# ministore-interconnect.net
KiCad netlist of a schematic drawn in EAGLE
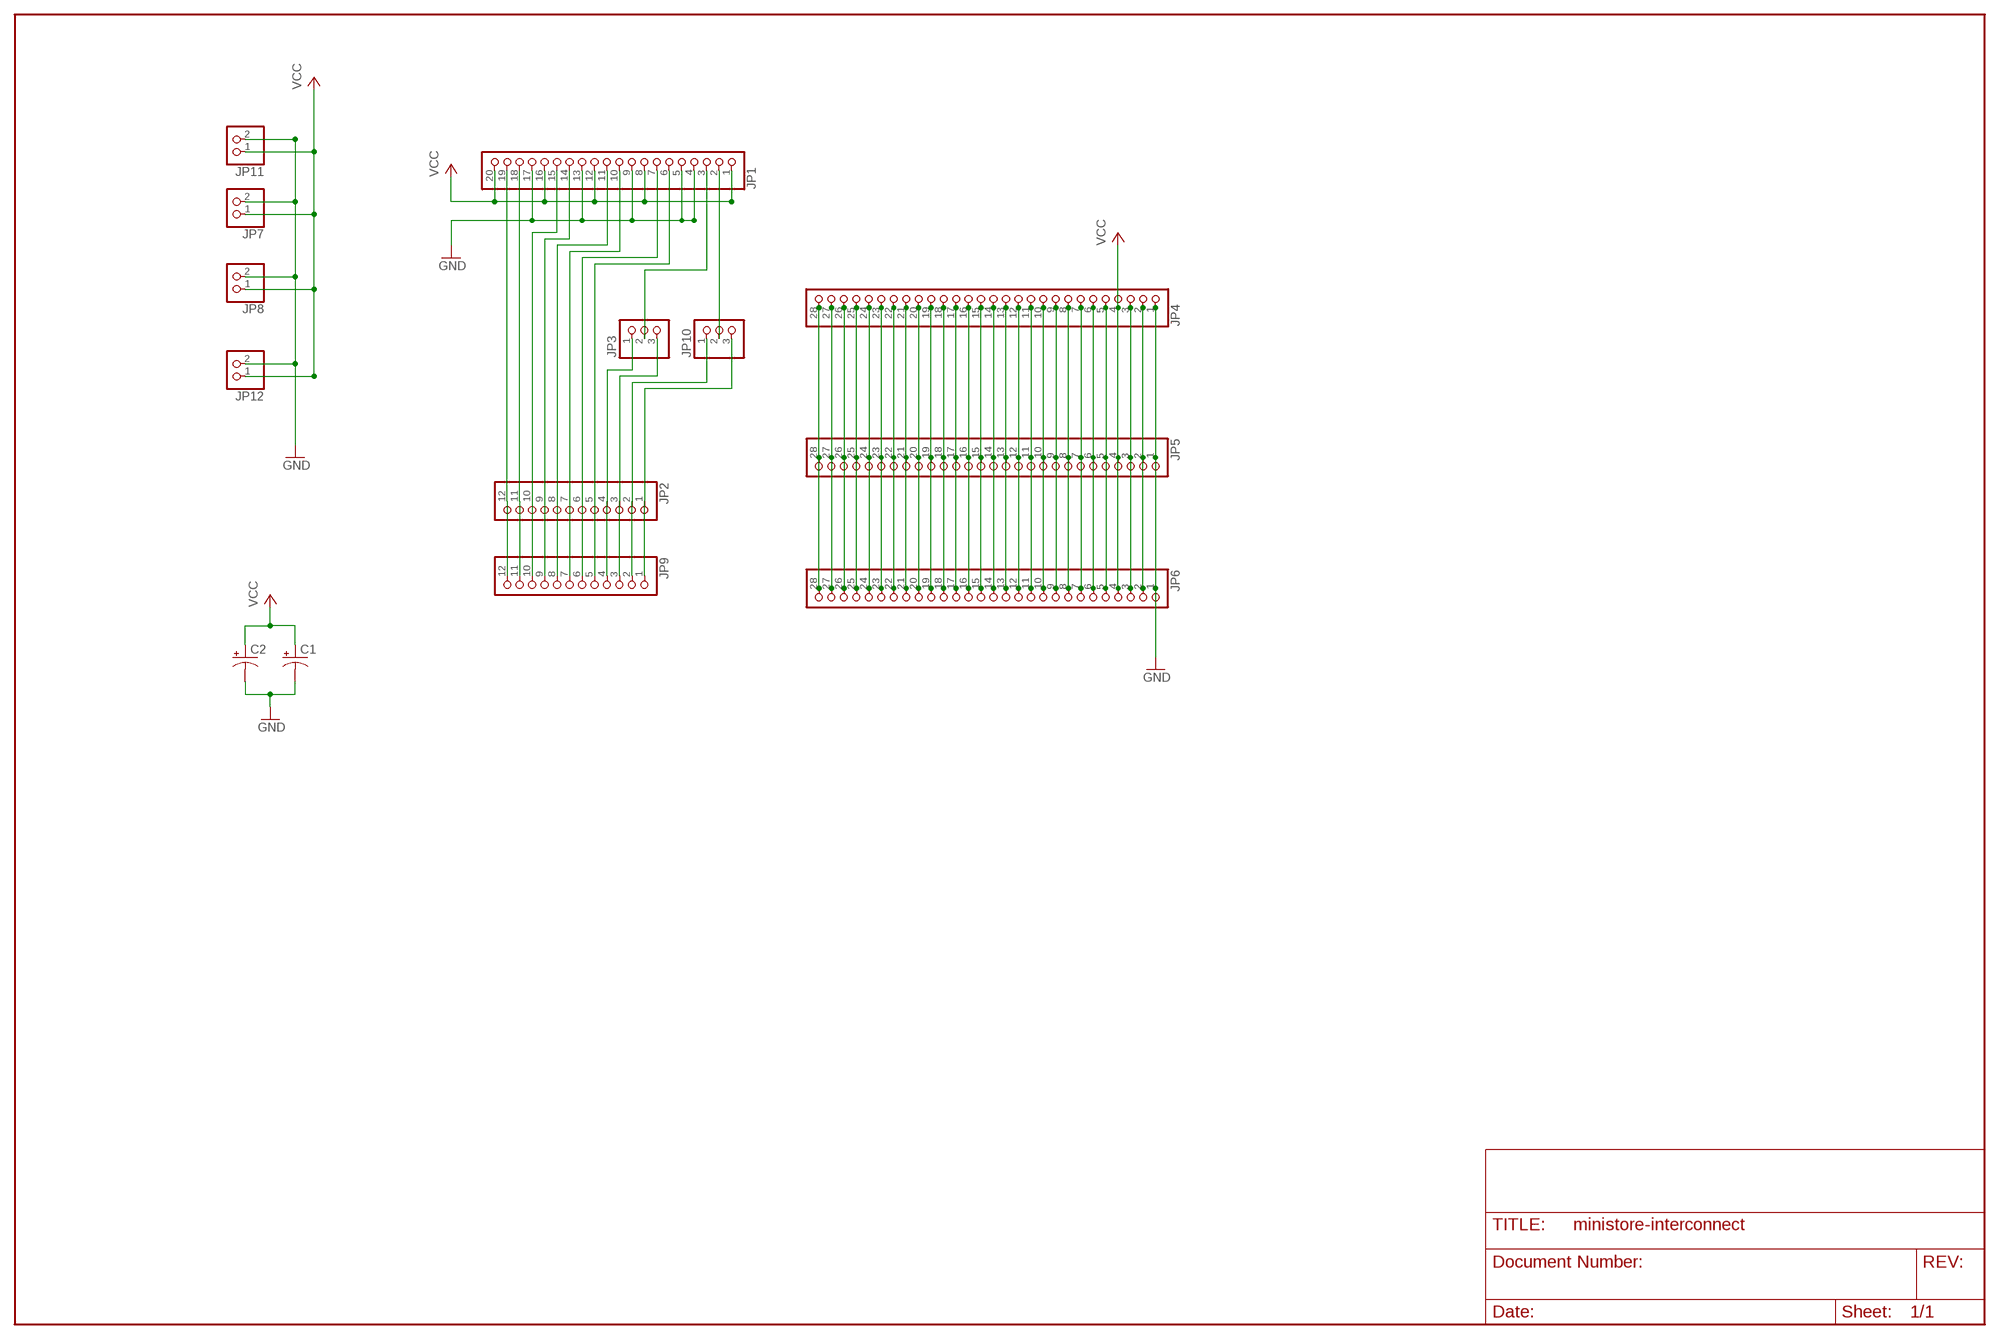
[diagram p0: schematic, sheet 1]

(export (version "E")
  (design (tool "Eeschema 10.0.6"))
  (components
    (comp (ref "C1")
      (value "CPOL-USE15-6AXIAL")
      (footprint "eagle-import:E15-6")
      (libsource (lib "eagle-import") (part "CPOL-USE15-6AXIAL"))
    )
    (comp (ref "C2")
      (value "CPOL-USE15-6AXIAL")
      (footprint "eagle-import:E15-6")
      (libsource (lib "eagle-import") (part "CPOL-USE15-6AXIAL"))
    )
    (comp (ref "JP1")
      (value "PINHD-1X20")
      (footprint "eagle-import:1X20")
      (libsource (lib "eagle-import") (part "PINHD-1X20"))
    )
    (comp (ref "JP2")
      (value "PINHD-1X12")
      (footprint "eagle-import:1X12")
      (libsource (lib "eagle-import") (part "PINHD-1X12"))
    )
    (comp (ref "JP3")
      (value "PINHD-1X3")
      (footprint "eagle-import:1X03")
      (libsource (lib "eagle-import") (part "PINHD-1X3"))
    )
    (comp (ref "JP4")
      (value "PINHD-1X28")
      (footprint "eagle-import:1X28")
      (libsource (lib "eagle-import") (part "PINHD-1X28"))
    )
    (comp (ref "JP5")
      (value "PINHD-1X28")
      (footprint "eagle-import:1X28")
      (libsource (lib "eagle-import") (part "PINHD-1X28"))
    )
    (comp (ref "JP6")
      (value "PINHD-1X28")
      (footprint "eagle-import:1X28")
      (libsource (lib "eagle-import") (part "PINHD-1X28"))
    )
    (comp (ref "JP7")
      (value "PINHD-1X2")
      (footprint "eagle-import:1X02")
      (libsource (lib "eagle-import") (part "PINHD-1X2"))
    )
    (comp (ref "JP8")
      (value "PINHD-1X2")
      (footprint "eagle-import:1X02")
      (libsource (lib "eagle-import") (part "PINHD-1X2"))
    )
    (comp (ref "JP9")
      (value "PINHD-1X12")
      (footprint "eagle-import:1X12")
      (libsource (lib "eagle-import") (part "PINHD-1X12"))
    )
    (comp (ref "JP10")
      (value "PINHD-1X3")
      (footprint "eagle-import:1X03")
      (libsource (lib "eagle-import") (part "PINHD-1X3"))
    )
    (comp (ref "JP11")
      (value "PINHD-1X2")
      (footprint "eagle-import:1X02")
      (libsource (lib "eagle-import") (part "PINHD-1X2"))
    )
    (comp (ref "JP12")
      (value "PINHD-1X2")
      (footprint "eagle-import:1X02")
      (libsource (lib "eagle-import") (part "PINHD-1X2"))
    )
  )
  (nets
    (net (code "1") (name "GND") (class "Default")
      (node (ref "C1") (pin "-") (pinfunction "-_-") (pintype "passive"))
      (node (ref "C2") (pin "-") (pinfunction "-_-") (pintype "passive"))
      (node (ref "JP1") (pin "13") (pinfunction "13_13") (pintype "passive"))
      (node (ref "JP1") (pin "17") (pinfunction "17_17") (pintype "passive"))
      (node (ref "JP1") (pin "4") (pinfunction "4_4") (pintype "passive"))
      (node (ref "JP1") (pin "5") (pinfunction "5_5") (pintype "passive"))
      (node (ref "JP1") (pin "9") (pinfunction "9_9") (pintype "passive"))
      (node (ref "JP11") (pin "2") (pinfunction "2_2") (pintype "passive"))
      (node (ref "JP12") (pin "2") (pinfunction "2_2") (pintype "passive"))
      (node (ref "JP4") (pin "1") (pinfunction "1_1") (pintype "passive"))
      (node (ref "JP5") (pin "1") (pinfunction "1_1") (pintype "passive"))
      (node (ref "JP6") (pin "1") (pinfunction "1_1") (pintype "passive"))
      (node (ref "JP7") (pin "2") (pinfunction "2_2") (pintype "passive"))
      (node (ref "JP8") (pin "2") (pinfunction "2_2") (pintype "passive"))
    )
    (net (code "2") (name "Net-(JP1-Pad2)") (class "Default")
      (node (ref "JP1") (pin "2") (pinfunction "2_2") (pintype "passive"))
      (node (ref "JP10") (pin "2") (pinfunction "2_2") (pintype "passive"))
    )
    (net (code "3") (name "Net-(JP1-Pad3)") (class "Default")
      (node (ref "JP1") (pin "3") (pinfunction "3_3") (pintype "passive"))
      (node (ref "JP3") (pin "2") (pinfunction "2_2") (pintype "passive"))
    )
    (net (code "4") (name "Net-(JP1-Pad6)") (class "Default")
      (node (ref "JP1") (pin "6") (pinfunction "6_6") (pintype "passive"))
      (node (ref "JP2") (pin "5") (pinfunction "5_5") (pintype "passive"))
      (node (ref "JP9") (pin "5") (pinfunction "5_5") (pintype "passive"))
    )
    (net (code "5") (name "Net-(JP1-Pad7)") (class "Default")
      (node (ref "JP1") (pin "7") (pinfunction "7_7") (pintype "passive"))
      (node (ref "JP2") (pin "6") (pinfunction "6_6") (pintype "passive"))
      (node (ref "JP9") (pin "6") (pinfunction "6_6") (pintype "passive"))
    )
    (net (code "6") (name "Net-(JP1-Pad10)") (class "Default")
      (node (ref "JP1") (pin "10") (pinfunction "10_10") (pintype "passive"))
      (node (ref "JP2") (pin "7") (pinfunction "7_7") (pintype "passive"))
      (node (ref "JP9") (pin "7") (pinfunction "7_7") (pintype "passive"))
    )
    (net (code "7") (name "Net-(JP1-Pad11)") (class "Default")
      (node (ref "JP1") (pin "11") (pinfunction "11_11") (pintype "passive"))
      (node (ref "JP2") (pin "8") (pinfunction "8_8") (pintype "passive"))
      (node (ref "JP9") (pin "8") (pinfunction "8_8") (pintype "passive"))
    )
    (net (code "8") (name "Net-(JP1-Pad14)") (class "Default")
      (node (ref "JP1") (pin "14") (pinfunction "14_14") (pintype "passive"))
      (node (ref "JP2") (pin "9") (pinfunction "9_9") (pintype "passive"))
      (node (ref "JP9") (pin "9") (pinfunction "9_9") (pintype "passive"))
    )
    (net (code "9") (name "Net-(JP1-Pad15)") (class "Default")
      (node (ref "JP1") (pin "15") (pinfunction "15_15") (pintype "passive"))
      (node (ref "JP2") (pin "10") (pinfunction "10_10") (pintype "passive"))
      (node (ref "JP9") (pin "10") (pinfunction "10_10") (pintype "passive"))
    )
    (net (code "10") (name "Net-(JP1-Pad18)") (class "Default")
      (node (ref "JP1") (pin "18") (pinfunction "18_18") (pintype "passive"))
      (node (ref "JP2") (pin "11") (pinfunction "11_11") (pintype "passive"))
      (node (ref "JP9") (pin "11") (pinfunction "11_11") (pintype "passive"))
    )
    (net (code "11") (name "Net-(JP1-Pad19)") (class "Default")
      (node (ref "JP1") (pin "19") (pinfunction "19_19") (pintype "passive"))
      (node (ref "JP2") (pin "12") (pinfunction "12_12") (pintype "passive"))
      (node (ref "JP9") (pin "12") (pinfunction "12_12") (pintype "passive"))
    )
    (net (code "12") (name "Net-(JP2-Pad3)") (class "Default")
      (node (ref "JP2") (pin "3") (pinfunction "3_3") (pintype "passive"))
      (node (ref "JP3") (pin "3") (pinfunction "3_3") (pintype "passive"))
      (node (ref "JP9") (pin "3") (pinfunction "3_3") (pintype "passive"))
    )
    (net (code "13") (name "Net-(JP2-Pad4)") (class "Default")
      (node (ref "JP2") (pin "4") (pinfunction "4_4") (pintype "passive"))
      (node (ref "JP3") (pin "1") (pinfunction "1_1") (pintype "passive"))
      (node (ref "JP9") (pin "4") (pinfunction "4_4") (pintype "passive"))
    )
    (net (code "14") (name "Net-(JP4-Pad2)") (class "Default")
      (node (ref "JP4") (pin "2") (pinfunction "2_2") (pintype "passive"))
      (node (ref "JP5") (pin "2") (pinfunction "2_2") (pintype "passive"))
      (node (ref "JP6") (pin "2") (pinfunction "2_2") (pintype "passive"))
    )
    (net (code "15") (name "Net-(JP4-Pad3)") (class "Default")
      (node (ref "JP4") (pin "3") (pinfunction "3_3") (pintype "passive"))
      (node (ref "JP5") (pin "3") (pinfunction "3_3") (pintype "passive"))
      (node (ref "JP6") (pin "3") (pinfunction "3_3") (pintype "passive"))
    )
    (net (code "16") (name "Net-(JP4-Pad5)") (class "Default")
      (node (ref "JP4") (pin "5") (pinfunction "5_5") (pintype "passive"))
      (node (ref "JP5") (pin "5") (pinfunction "5_5") (pintype "passive"))
      (node (ref "JP6") (pin "5") (pinfunction "5_5") (pintype "passive"))
    )
    (net (code "17") (name "Net-(JP4-Pad6)") (class "Default")
      (node (ref "JP4") (pin "6") (pinfunction "6_6") (pintype "passive"))
      (node (ref "JP5") (pin "6") (pinfunction "6_6") (pintype "passive"))
      (node (ref "JP6") (pin "6") (pinfunction "6_6") (pintype "passive"))
    )
    (net (code "18") (name "Net-(JP4-Pad7)") (class "Default")
      (node (ref "JP4") (pin "7") (pinfunction "7_7") (pintype "passive"))
      (node (ref "JP5") (pin "7") (pinfunction "7_7") (pintype "passive"))
      (node (ref "JP6") (pin "7") (pinfunction "7_7") (pintype "passive"))
    )
    (net (code "19") (name "Net-(JP4-Pad8)") (class "Default")
      (node (ref "JP4") (pin "8") (pinfunction "8_8") (pintype "passive"))
      (node (ref "JP5") (pin "8") (pinfunction "8_8") (pintype "passive"))
      (node (ref "JP6") (pin "8") (pinfunction "8_8") (pintype "passive"))
    )
    (net (code "20") (name "Net-(JP4-Pad9)") (class "Default")
      (node (ref "JP4") (pin "9") (pinfunction "9_9") (pintype "passive"))
      (node (ref "JP5") (pin "9") (pinfunction "9_9") (pintype "passive"))
      (node (ref "JP6") (pin "9") (pinfunction "9_9") (pintype "passive"))
    )
    (net (code "21") (name "Net-(JP4-Pad10)") (class "Default")
      (node (ref "JP4") (pin "10") (pinfunction "10_10") (pintype "passive"))
      (node (ref "JP5") (pin "10") (pinfunction "10_10") (pintype "passive"))
      (node (ref "JP6") (pin "10") (pinfunction "10_10") (pintype "passive"))
    )
    (net (code "22") (name "Net-(JP4-Pad11)") (class "Default")
      (node (ref "JP4") (pin "11") (pinfunction "11_11") (pintype "passive"))
      (node (ref "JP5") (pin "11") (pinfunction "11_11") (pintype "passive"))
      (node (ref "JP6") (pin "11") (pinfunction "11_11") (pintype "passive"))
    )
    (net (code "23") (name "Net-(JP4-Pad12)") (class "Default")
      (node (ref "JP4") (pin "12") (pinfunction "12_12") (pintype "passive"))
      (node (ref "JP5") (pin "12") (pinfunction "12_12") (pintype "passive"))
      (node (ref "JP6") (pin "12") (pinfunction "12_12") (pintype "passive"))
    )
    (net (code "24") (name "Net-(JP4-Pad13)") (class "Default")
      (node (ref "JP4") (pin "13") (pinfunction "13_13") (pintype "passive"))
      (node (ref "JP5") (pin "13") (pinfunction "13_13") (pintype "passive"))
      (node (ref "JP6") (pin "13") (pinfunction "13_13") (pintype "passive"))
    )
    (net (code "25") (name "Net-(JP4-Pad14)") (class "Default")
      (node (ref "JP4") (pin "14") (pinfunction "14_14") (pintype "passive"))
      (node (ref "JP5") (pin "14") (pinfunction "14_14") (pintype "passive"))
      (node (ref "JP6") (pin "14") (pinfunction "14_14") (pintype "passive"))
    )
    (net (code "26") (name "Net-(JP4-Pad15)") (class "Default")
      (node (ref "JP4") (pin "15") (pinfunction "15_15") (pintype "passive"))
      (node (ref "JP5") (pin "15") (pinfunction "15_15") (pintype "passive"))
      (node (ref "JP6") (pin "15") (pinfunction "15_15") (pintype "passive"))
    )
    (net (code "27") (name "Net-(JP4-Pad16)") (class "Default")
      (node (ref "JP4") (pin "16") (pinfunction "16_16") (pintype "passive"))
      (node (ref "JP5") (pin "16") (pinfunction "16_16") (pintype "passive"))
      (node (ref "JP6") (pin "16") (pinfunction "16_16") (pintype "passive"))
    )
    (net (code "28") (name "Net-(JP4-Pad17)") (class "Default")
      (node (ref "JP4") (pin "17") (pinfunction "17_17") (pintype "passive"))
      (node (ref "JP5") (pin "17") (pinfunction "17_17") (pintype "passive"))
      (node (ref "JP6") (pin "17") (pinfunction "17_17") (pintype "passive"))
    )
    (net (code "29") (name "Net-(JP4-Pad18)") (class "Default")
      (node (ref "JP4") (pin "18") (pinfunction "18_18") (pintype "passive"))
      (node (ref "JP5") (pin "18") (pinfunction "18_18") (pintype "passive"))
      (node (ref "JP6") (pin "18") (pinfunction "18_18") (pintype "passive"))
    )
    (net (code "30") (name "Net-(JP4-Pad19)") (class "Default")
      (node (ref "JP4") (pin "19") (pinfunction "19_19") (pintype "passive"))
      (node (ref "JP5") (pin "19") (pinfunction "19_19") (pintype "passive"))
      (node (ref "JP6") (pin "19") (pinfunction "19_19") (pintype "passive"))
    )
    (net (code "31") (name "Net-(JP4-Pad20)") (class "Default")
      (node (ref "JP4") (pin "20") (pinfunction "20_20") (pintype "passive"))
      (node (ref "JP5") (pin "20") (pinfunction "20_20") (pintype "passive"))
      (node (ref "JP6") (pin "20") (pinfunction "20_20") (pintype "passive"))
    )
    (net (code "32") (name "Net-(JP4-Pad21)") (class "Default")
      (node (ref "JP4") (pin "21") (pinfunction "21_21") (pintype "passive"))
      (node (ref "JP5") (pin "21") (pinfunction "21_21") (pintype "passive"))
      (node (ref "JP6") (pin "21") (pinfunction "21_21") (pintype "passive"))
    )
    (net (code "33") (name "Net-(JP4-Pad22)") (class "Default")
      (node (ref "JP4") (pin "22") (pinfunction "22_22") (pintype "passive"))
      (node (ref "JP5") (pin "22") (pinfunction "22_22") (pintype "passive"))
      (node (ref "JP6") (pin "22") (pinfunction "22_22") (pintype "passive"))
    )
    (net (code "34") (name "Net-(JP4-Pad23)") (class "Default")
      (node (ref "JP4") (pin "23") (pinfunction "23_23") (pintype "passive"))
      (node (ref "JP5") (pin "23") (pinfunction "23_23") (pintype "passive"))
      (node (ref "JP6") (pin "23") (pinfunction "23_23") (pintype "passive"))
    )
    (net (code "35") (name "Net-(JP4-Pad24)") (class "Default")
      (node (ref "JP4") (pin "24") (pinfunction "24_24") (pintype "passive"))
      (node (ref "JP5") (pin "24") (pinfunction "24_24") (pintype "passive"))
      (node (ref "JP6") (pin "24") (pinfunction "24_24") (pintype "passive"))
    )
    (net (code "36") (name "Net-(JP4-Pad25)") (class "Default")
      (node (ref "JP4") (pin "25") (pinfunction "25_25") (pintype "passive"))
      (node (ref "JP5") (pin "25") (pinfunction "25_25") (pintype "passive"))
      (node (ref "JP6") (pin "25") (pinfunction "25_25") (pintype "passive"))
    )
    (net (code "37") (name "Net-(JP4-Pad26)") (class "Default")
      (node (ref "JP4") (pin "26") (pinfunction "26_26") (pintype "passive"))
      (node (ref "JP5") (pin "26") (pinfunction "26_26") (pintype "passive"))
      (node (ref "JP6") (pin "26") (pinfunction "26_26") (pintype "passive"))
    )
    (net (code "38") (name "Net-(JP4-Pad27)") (class "Default")
      (node (ref "JP4") (pin "27") (pinfunction "27_27") (pintype "passive"))
      (node (ref "JP5") (pin "27") (pinfunction "27_27") (pintype "passive"))
      (node (ref "JP6") (pin "27") (pinfunction "27_27") (pintype "passive"))
    )
    (net (code "39") (name "Net-(JP4-Pad28)") (class "Default")
      (node (ref "JP4") (pin "28") (pinfunction "28_28") (pintype "passive"))
      (node (ref "JP5") (pin "28") (pinfunction "28_28") (pintype "passive"))
      (node (ref "JP6") (pin "28") (pinfunction "28_28") (pintype "passive"))
    )
    (net (code "40") (name "Net-(JP10-Pad1)") (class "Default")
      (node (ref "JP10") (pin "1") (pinfunction "1_1") (pintype "passive"))
      (node (ref "JP2") (pin "2") (pinfunction "2_2") (pintype "passive"))
      (node (ref "JP9") (pin "2") (pinfunction "2_2") (pintype "passive"))
    )
    (net (code "41") (name "Net-(JP10-Pad3)") (class "Default")
      (node (ref "JP10") (pin "3") (pinfunction "3_3") (pintype "passive"))
      (node (ref "JP2") (pin "1") (pinfunction "1_1") (pintype "passive"))
      (node (ref "JP9") (pin "1") (pinfunction "1_1") (pintype "passive"))
    )
    (net (code "42") (name "VCC") (class "Default")
      (node (ref "C1") (pin "+") (pinfunction "+_+") (pintype "passive"))
      (node (ref "C2") (pin "+") (pinfunction "+_+") (pintype "passive"))
      (node (ref "JP1") (pin "1") (pinfunction "1_1") (pintype "passive"))
      (node (ref "JP1") (pin "12") (pinfunction "12_12") (pintype "passive"))
      (node (ref "JP1") (pin "16") (pinfunction "16_16") (pintype "passive"))
      (node (ref "JP1") (pin "20") (pinfunction "20_20") (pintype "passive"))
      (node (ref "JP1") (pin "8") (pinfunction "8_8") (pintype "passive"))
      (node (ref "JP11") (pin "1") (pinfunction "1_1") (pintype "passive"))
      (node (ref "JP12") (pin "1") (pinfunction "1_1") (pintype "passive"))
      (node (ref "JP4") (pin "4") (pinfunction "4_4") (pintype "passive"))
      (node (ref "JP5") (pin "4") (pinfunction "4_4") (pintype "passive"))
      (node (ref "JP6") (pin "4") (pinfunction "4_4") (pintype "passive"))
      (node (ref "JP7") (pin "1") (pinfunction "1_1") (pintype "passive"))
      (node (ref "JP8") (pin "1") (pinfunction "1_1") (pintype "passive"))
    )
  )
)
